# LoRa-module.net
KiCad netlist of a schematic drawn in Altium Designer
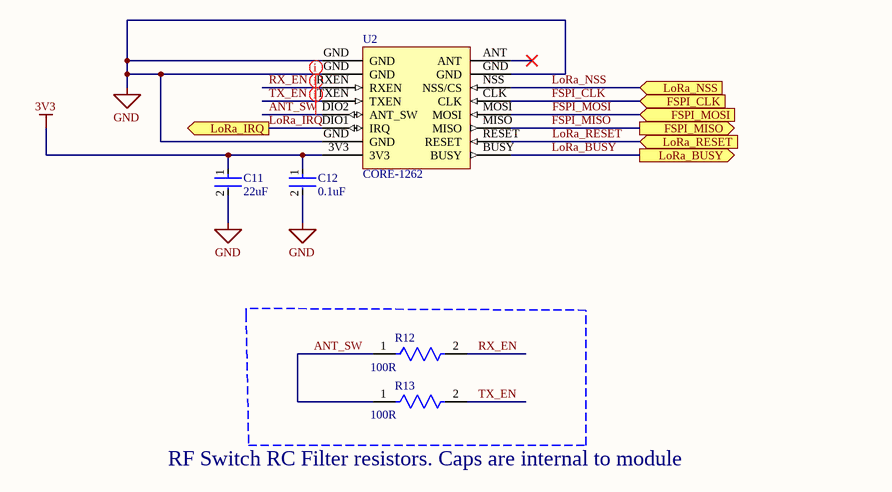
[diagram p0: LoRa-module.SchDoc]

(export (version "E")
  (design (tool "Eeschema 10.0.6"))
  (components
    (comp (ref "C11")
      (value "22uF")
      (footprint "FP-GRM21B-0_15-MFG")
      (description "Chip Multilayer Ceramic Capacitors for General Purpose, 0805, 22uF, X5R, 15%, 20%, 6.3V")
      (fields (field (name "VOLTAGE") "6.3V") (field (name "TOLERANCE") "20%"))
      (libsource (lib "Altium Content Vault") (part "b4654b650e69147ec39a6b967a45e02"))
    )
    (comp (ref "C12")
      (value "0.1uF")
      (footprint "FP-GCM21B-0_15-MFG")
      (description "Ceramic Capacitor for Automotive 100nF ±10% 100VDC X7R 0805 Embossed T/R")
      (fields (field (name "TOLERANCE") "10%") (field (name "VOLTAGE") "100V"))
      (libsource (lib "Altium Content Vault") (part "02cd4be3c70576c341d710602a673aa"))
    )
    (comp (ref "R12")
      (value "RMCF0805FT100R")
      (footprint "FP-RMCF0805-IPC_A")
      (description "100Ω ±1% 0.125W 0805 Thick Film Chip Resistor AEC-Q200 compliant")
      (fields (field (name "TOLERANCE") "1%") (field (name "RESISTANCE") "100R"))
      (libsource (lib "Altium Content Vault") (part "1029c3af85768c4190bb7ad29bc67b5"))
    )
    (comp (ref "R13")
      (value "RMCF0805FT100R")
      (footprint "FP-RMCF0805-IPC_A")
      (description "100Ω ±1% 0.125W 0805 Thick Film Chip Resistor AEC-Q200 compliant")
      (fields (field (name "TOLERANCE") "1%") (field (name "RESISTANCE") "100R"))
      (libsource (lib "Altium Content Vault") (part "1029c3af85768c4190bb7ad29bc67b5"))
    )
    (comp (ref "U2")
      (value "CORE-1262")
      (footprint "WAVE-20855-Core1262")
      (description "LoRa HF module")
      (libsource (lib "Core1262") (part "CORE-1262"))
    )
  )
  (nets
    (net (code "1") (name "/ANT_SW") (class "Default")
      (node (ref "R12") (pin "1") (pinfunction "1_1") (pintype "passive"))
      (node (ref "R13") (pin "1") (pinfunction "1_1") (pintype "passive"))
      (node (ref "U2") (pin "DIO2") (pinfunction "ANT_SW_DIO2") (pintype "bidirectional"))
    )
    (net (code "2") (name "/FSPI_CLK") (class "Default")
      (node (ref "U2") (pin "CLK") (pinfunction "CLK_CLK") (pintype "input"))
    )
    (net (code "3") (name "/FSPI_MISO") (class "Default")
      (node (ref "U2") (pin "MISO") (pinfunction "MISO_MISO") (pintype "output"))
    )
    (net (code "4") (name "/FSPI_MOSI") (class "Default")
      (node (ref "U2") (pin "MOSI") (pinfunction "MOSI_MOSI") (pintype "input"))
    )
    (net (code "5") (name "/LoRa_BUSY") (class "Default")
      (node (ref "U2") (pin "BUSY") (pinfunction "BUSY_BUSY") (pintype "output"))
    )
    (net (code "6") (name "/LoRa_IRQ") (class "Default")
      (node (ref "U2") (pin "DIO1") (pinfunction "IRQ_DIO1") (pintype "bidirectional"))
    )
    (net (code "7") (name "/LoRa_NSS") (class "Default")
      (node (ref "U2") (pin "NSS") (pinfunction "NSS/CS_NSS") (pintype "input"))
    )
    (net (code "8") (name "/LoRa_RESET") (class "Default")
      (node (ref "U2") (pin "RESET") (pinfunction "RESET_RESET") (pintype "input"))
    )
    (net (code "9") (name "/RX_EN") (class "Default")
      (node (ref "R12") (pin "2") (pinfunction "2_2") (pintype "passive"))
      (node (ref "U2") (pin "RXEN") (pinfunction "RXEN_RXEN") (pintype "input"))
    )
    (net (code "10") (name "/TX_EN") (class "Default")
      (node (ref "R13") (pin "2") (pinfunction "2_2") (pintype "passive"))
      (node (ref "U2") (pin "TXEN") (pinfunction "TXEN_TXEN") (pintype "input"))
    )
    (net (code "11") (name "3V3") (class "Default")
      (node (ref "C11") (pin "1") (pinfunction "1_1") (pintype "passive"))
      (node (ref "C12") (pin "1") (pinfunction "1_1") (pintype "passive"))
      (node (ref "U2") (pin "3V3") (pinfunction "3V3_3V3") (pintype "power_in"))
    )
    (net (code "12") (name "GND") (class "Default")
      (node (ref "C11") (pin "2") (pinfunction "2_2") (pintype "passive"))
      (node (ref "C12") (pin "2") (pinfunction "2_2") (pintype "passive"))
      (node (ref "U2") (pin "GND") (pinfunction "GND_GND") (pintype "power_in"))
    )
    (net (code "13") (name "unconnected-(U2-PadANT)") (class "Default")
      (node (ref "U2") (pin "ANT") (pinfunction "ANT_ANT") (pintype "passive"))
    )
    (net (code "14") (name "unconnected-(U2-PadGND)") (class "Default")
      (node (ref "U2") (pin "GND") (pinfunction "GND_GND") (pintype "power_in"))
    )
  )
)
